# LED_Transistor.net
KiCad netlist of a schematic drawn in Altium Designer
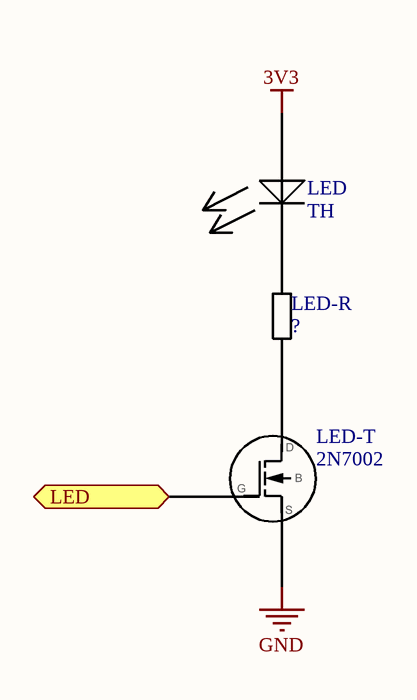
[diagram p0: LED+Transistor.SchDoc]

(export (version "E")
  (design (tool "Eeschema 10.0.6"))
  (components
    (comp (ref "LED") (value "TH") (footprint "LED 3mm") (libsource (lib "LEDs") (part "LED")))
    (comp (ref "LED-R")
      (value "?")
      (footprint "R 0805 / 2012")
      (libsource (lib "Standard") (part "Resistor"))
    )
    (comp (ref "LED-T")
      (value "2N7002")
      (footprint "SOT-23-3")
      (description "N-FET")
      (libsource (lib "ICs") (part "2N7002"))
    )
  )
  (nets
    (net (code "1") (name "/LED") (class "Default")
      (node (ref "LED-T") (pin "1") (pinfunction "1_1") (pintype "passive"))
    )
    (net (code "2") (name "3V3") (class "Default")
      (node (ref "LED") (pin "1") (pinfunction "+_1") (pintype "passive"))
    )
    (net (code "3") (name "GND") (class "Default")
      (node (ref "LED-T") (pin "2") (pinfunction "2_2") (pintype "passive"))
    )
    (net (code "4") (name "Net-(LED--)") (class "Default")
      (node (ref "LED") (pin "2") (pinfunction "-_2") (pintype "passive"))
      (node (ref "LED-R") (pin "2") (pinfunction "2_2") (pintype "passive"))
    )
    (net (code "5") (name "Net-(LED-R-Pad1)") (class "Default")
      (node (ref "LED-R") (pin "1") (pinfunction "1_1") (pintype "passive"))
      (node (ref "LED-T") (pin "3") (pinfunction "3_3") (pintype "passive"))
    )
  )
)
